# Mojo.net
KiCad netlist of a schematic drawn in Altium Designer
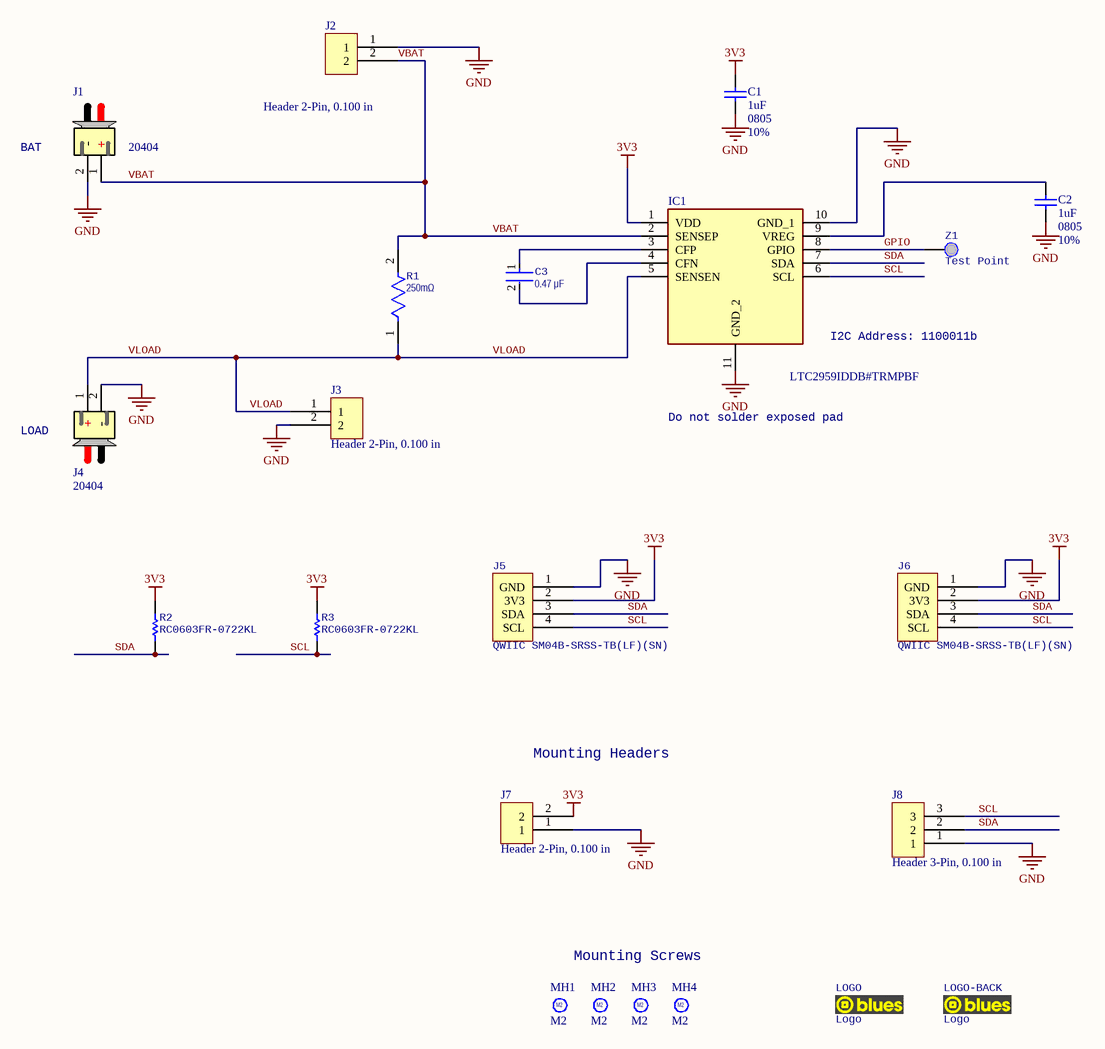
[diagram p0: Mojo.SchDoc]

(export (version "E")
  (design (tool "Eeschema 10.0.6"))
  (components
    (comp (ref "C1")
      (value "GRM216R61E105KA12D")
      (footprint "CAPC2013X70X45NL10T25")
      (fields
        (field (name "MANUFACTURER") "Murata")
        (field (name "CAPACITANCE") "1uF")
        (field (name "CASE/PACKAGE") "0805")
        (field (name "VOLTAGE") "25V")
        (field (name "TOLERANCE") "10%")
      )
      (libsource (lib "Altium Content Vault") (part "CAP"))
    )
    (comp (ref "C2")
      (value "GRM216R61E105KA12D")
      (footprint "CAPC2013X70X45NL10T25")
      (fields
        (field (name "MANUFACTURER") "Murata")
        (field (name "CAPACITANCE") "1uF")
        (field (name "CASE/PACKAGE") "0805")
        (field (name "VOLTAGE") "25V")
        (field (name "TOLERANCE") "10%")
      )
      (libsource (lib "Altium Content Vault") (part "CAP"))
    )
    (comp (ref "C3")
      (value "0.47 μF")
      (footprint "FP-C0805C-DN-MFG")
      (description "CAP CER 0.47UF 50V 10% X7R 0805")
      (fields
        (field (name "MANUFACTURER") "KEMET")
        (field (name "MANUFACTURER PART NUMBER") "C0805C474K5RACTU")
      )
      (libsource (lib "Altium Content Vault") (part "b4654b650e69147ec39a6b967a45e02"))
    )
    (comp (ref "IC1")
      (value "LTC2959IDDB#TRMPBF")
      (footprint "samacsys:SON50P200X300X80-11N-D")
      (description "Ultra-low-power Battery Gas Gaug")
      (fields
        (field (name "MOUSER PART NUMBER") "584-LTC2959IDDBTRMPB")
        (field (name "MANUFACTURER") "Analog Devices")
      )
      (libsource (lib "*") (part "LTC2959IDDB#TRMPBF"))
    )
    (comp (ref "J1")
      (value "20404")
      (footprint "BAT-AF-S2B-PH-SM4")
      (fields (field (name "MANUFACTURER") "4UCON"))
      (libsource (lib "") (part "BAT-PH-ADAFRUIT-SMT-RA_1"))
    )
    (comp (ref "J2")
      (value "Header 2-Pin, 0.100 in")
      (footprint "HEADER_AA_002")
      (description "Header 2-Pin, 0.100 inch (0.230 inch head)")
      (fields (field (name "MANUFACTURER") "Sullins") (field (name "MANUFACTURER PART NUMBER") "PEC02SAAN"))
      (libsource (lib "") (part "HEADER_AA_2_1"))
    )
    (comp (ref "J3")
      (value "Header 2-Pin, 0.100 in")
      (footprint "HEADER_AA_002")
      (description "Header 2-Pin, 0.100 inch (0.230 inch head)")
      (fields (field (name "MANUFACTURER") "Sullins") (field (name "MANUFACTURER PART NUMBER") "PEC02SAAN"))
      (libsource (lib "") (part "HEADER_AA_2_2"))
    )
    (comp (ref "J4")
      (value "20404")
      (footprint "BAT-AF-S2B-PH-SM4")
      (fields (field (name "MANUFACTURER") "4UCON"))
      (libsource (lib "TBL Battery Holders") (part "BAT-PH-ADAFRUIT-SMT-RA"))
    )
    (comp (ref "J5")
      (value "QWIIC SM04B-SRSS-TB(LF)(SN)")
      (footprint "QWIIC_SM04B-SRSS")
      (description "CONN HEADER SH 4POS SIDE 1MM TIN QWIIC pinout")
      (fields
        (field (name "MANUFACTURER") "JST")
        (field (name "MANUFACTURER PART NUMBER") "SM04B-SRSS-TB(LF)(SN)")
      )
      (libsource (lib "TBL Connectors") (part "QWIIC_SM04B-SRSS"))
    )
    (comp (ref "J6")
      (value "QWIIC SM04B-SRSS-TB(LF)(SN)")
      (footprint "QWIIC_SM04B-SRSS")
      (description "CONN HEADER SH 4POS SIDE 1MM TIN QWIIC pinout")
      (fields
        (field (name "MANUFACTURER") "JST")
        (field (name "MANUFACTURER PART NUMBER") "SM04B-SRSS-TB(LF)(SN)")
      )
      (libsource (lib "TBL Connectors") (part "QWIIC_SM04B-SRSS"))
    )
    (comp (ref "J7")
      (value "Header 2-Pin, 0.100 in")
      (footprint "HEADER_AA_002")
      (description "Header 2-Pin, 0.100 inch (0.230 inch head)")
      (fields (field (name "MANUFACTURER") "Sullins") (field (name "MANUFACTURER PART NUMBER") "PEC02SAAN"))
      (libsource (lib "TBLI-Headers") (part "HEADER_AA_2"))
    )
    (comp (ref "J8")
      (value "Header 3-Pin, 0.100 in")
      (footprint "HEADER_AA_003")
      (description "Header 3-Pin, 0.100 inch (0.230 inch head)")
      (fields (field (name "MANUFACTURER") "Sullins") (field (name "MANUFACTURER PART NUMBER") "PEC03SAAN"))
      (libsource (lib "TBLI-Headers") (part "HEADER_AA_3"))
    )
    (comp (ref "LOGO")
      (value "Logo")
      (footprint "LOGO_BLUES_WIRELESS_v2")
      (description "Logo, Blues Wireless")
      (libsource (lib "Blues Wireless Library") (part "LOGO_BLUES_WIRELESS_V2"))
    )
    (comp (ref "LOGO-BACK")
      (value "Logo")
      (footprint "LOGO_BLUES_WIRELESS_v2")
      (description "Logo, Blues Wireless")
      (libsource (lib "Blues Wireless Library") (part "LOGO_BLUES_WIRELESS_V2"))
    )
    (comp (ref "MH1")
      (value "M2")
      (footprint "HOLE_2MM")
      (description "Bare Hole, M2")
      (libsource (lib "TBL Mechanical") (part "Bare Hole M2"))
    )
    (comp (ref "MH2")
      (value "M2")
      (footprint "HOLE_2MM")
      (description "Bare Hole, M2")
      (libsource (lib "TBL Mechanical") (part "Bare Hole M2"))
    )
    (comp (ref "MH3")
      (value "M2")
      (footprint "HOLE_2MM")
      (description "Bare Hole, M2")
      (libsource (lib "TBL Mechanical") (part "Bare Hole M2"))
    )
    (comp (ref "MH4")
      (value "M2")
      (footprint "HOLE_2MM")
      (description "Bare Hole, M2")
      (libsource (lib "TBL Mechanical") (part "Bare Hole M2"))
    )
    (comp (ref "R1")
      (value "WSL2010R2500FEA")
      (footprint "FP-WSL2010-0_508-MFG")
      (description "0R250 Metal Strp 2010 1% 1/2W 75Ppm/ C WSL2010R2500FEA")
      (fields
        (field (name "TOLERANCE") "1%")
        (field (name "RESISTANCE") "250mΩ")
        (field (name "MANUFACTURER") "Vishay Dale")
      )
      (libsource (lib "TBL Passives") (part "RES_2020_0R250"))
    )
    (comp (ref "R2")
      (value "RC0603FR-0722KL")
      (footprint "RESC1608X55X25LL10T15")
      (description "Chip Resistor, 22 KOhm, +/- 1%, 0.1 W, -55 to 155 degC, 0603 (1608 Metric), RoHS, Tape and Reel")
      (fields (field (name "TOLERANCE") "10%"))
      (libsource (lib "Altium Content Vault") (part "RES-2"))
    )
    (comp (ref "R3")
      (value "RC0603FR-0722KL")
      (footprint "RESC1608X55X25LL10T15")
      (description "Chip Resistor, 22 KOhm, +/- 1%, 0.1 W, -55 to 155 degC, 0603 (1608 Metric), RoHS, Tape and Reel")
      (fields (field (name "TOLERANCE") "10%"))
      (libsource (lib "Altium Content Vault") (part "RES-2"))
    )
    (comp (ref "Z1")
      (value "Test Point")
      (footprint "testp_40pad")
      (description "Test point")
      (libsource (lib "TBL Common") (part "test_pt"))
    )
  )
  (nets
    (net (code "1") (name "/GPIO") (class "Default")
      (node (ref "IC1") (pin "8") (pinfunction "GPIO_8") (pintype "passive"))
      (node (ref "Z1") (pin "1") (pinfunction "1_1") (pintype "passive"))
    )
    (net (code "2") (name "/SCL") (class "Default")
      (node (ref "IC1") (pin "6") (pinfunction "SCL_6") (pintype "passive"))
      (node (ref "J5") (pin "4") (pinfunction "SCL_4") (pintype "passive"))
      (node (ref "J6") (pin "4") (pinfunction "SCL_4") (pintype "passive"))
      (node (ref "J8") (pin "3") (pinfunction "3_3") (pintype "passive"))
      (node (ref "R3") (pin "1") (pinfunction "1_1") (pintype "passive"))
    )
    (net (code "3") (name "/SDA") (class "Default")
      (node (ref "IC1") (pin "7") (pinfunction "SDA_7") (pintype "passive"))
      (node (ref "J5") (pin "3") (pinfunction "SDA_3") (pintype "passive"))
      (node (ref "J6") (pin "3") (pinfunction "SDA_3") (pintype "passive"))
      (node (ref "J8") (pin "2") (pinfunction "2_2") (pintype "passive"))
      (node (ref "R2") (pin "1") (pinfunction "1_1") (pintype "passive"))
    )
    (net (code "4") (name "/VBAT") (class "Default")
      (node (ref "IC1") (pin "2") (pinfunction "SENSEP_2") (pintype "passive"))
      (node (ref "J1") (pin "1") (pinfunction "+_1") (pintype "passive"))
      (node (ref "J2") (pin "2") (pinfunction "2_2") (pintype "passive"))
      (node (ref "R1") (pin "2") (pinfunction "2_2") (pintype "passive"))
    )
    (net (code "5") (name "/VLOAD") (class "Default")
      (node (ref "IC1") (pin "5") (pinfunction "SENSEN_5") (pintype "passive"))
      (node (ref "J3") (pin "1") (pinfunction "1_1") (pintype "passive"))
      (node (ref "J4") (pin "1") (pinfunction "+_1") (pintype "passive"))
      (node (ref "R1") (pin "1") (pinfunction "1_1") (pintype "passive"))
    )
    (net (code "6") (name "3V3") (class "Default")
      (node (ref "C1") (pin "2") (pinfunction "2_2") (pintype "passive"))
      (node (ref "IC1") (pin "1") (pinfunction "VDD_1") (pintype "passive"))
      (node (ref "J5") (pin "2") (pinfunction "3V3_2") (pintype "passive"))
      (node (ref "J6") (pin "2") (pinfunction "3V3_2") (pintype "passive"))
      (node (ref "J7") (pin "2") (pinfunction "2_2") (pintype "passive"))
      (node (ref "R2") (pin "2") (pinfunction "2_2") (pintype "passive"))
      (node (ref "R3") (pin "2") (pinfunction "2_2") (pintype "passive"))
    )
    (net (code "7") (name "GND") (class "Default")
      (node (ref "C1") (pin "1") (pinfunction "1_1") (pintype "passive"))
      (node (ref "C2") (pin "1") (pinfunction "1_1") (pintype "passive"))
      (node (ref "IC1") (pin "10") (pinfunction "GND_1_10") (pintype "passive"))
      (node (ref "IC1") (pin "11") (pinfunction "GND_2_11") (pintype "passive"))
      (node (ref "J1") (pin "2") (pinfunction "-_2") (pintype "passive"))
      (node (ref "J2") (pin "1") (pinfunction "1_1") (pintype "passive"))
      (node (ref "J3") (pin "2") (pinfunction "2_2") (pintype "passive"))
      (node (ref "J4") (pin "2") (pinfunction "-_2") (pintype "passive"))
      (node (ref "J5") (pin "1") (pinfunction "GND_1") (pintype "passive"))
      (node (ref "J6") (pin "1") (pinfunction "GND_1") (pintype "passive"))
      (node (ref "J7") (pin "1") (pinfunction "1_1") (pintype "passive"))
      (node (ref "J8") (pin "1") (pinfunction "1_1") (pintype "passive"))
    )
    (net (code "8") (name "Net-(IC1-CFN)") (class "Default")
      (node (ref "C3") (pin "2") (pinfunction "2_2") (pintype "passive"))
      (node (ref "IC1") (pin "4") (pinfunction "CFN_4") (pintype "passive"))
    )
    (net (code "9") (name "Net-(IC1-CFP)") (class "Default")
      (node (ref "C3") (pin "1") (pinfunction "1_1") (pintype "passive"))
      (node (ref "IC1") (pin "3") (pinfunction "CFP_3") (pintype "passive"))
    )
    (net (code "10") (name "Net-(IC1-VREG)") (class "Default")
      (node (ref "C2") (pin "2") (pinfunction "2_2") (pintype "passive"))
      (node (ref "IC1") (pin "9") (pinfunction "VREG_9") (pintype "passive"))
    )
  )
)
